# GWLSensor_v10.net
KiCad netlist of a schematic drawn in EAGLE
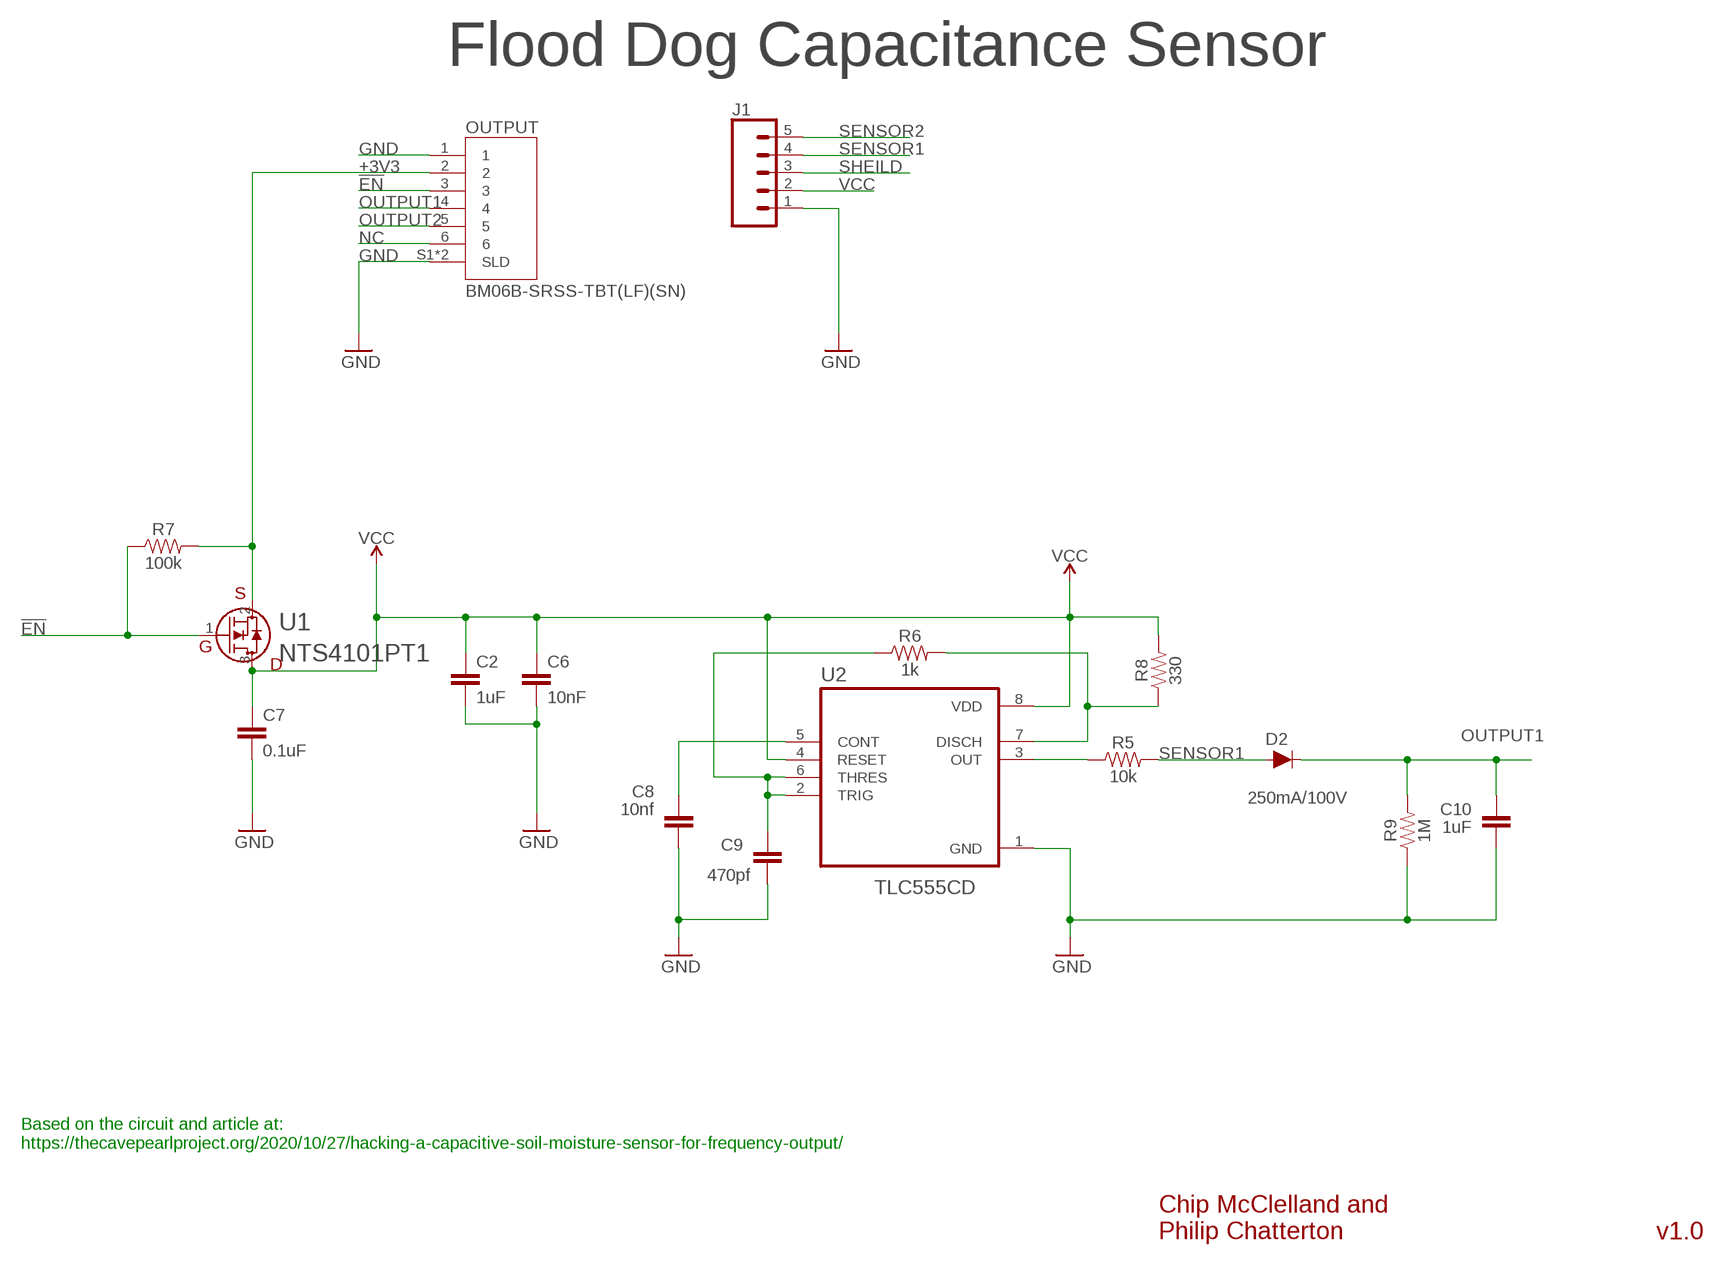
[diagram p0: schematic, sheet 1]

(export (version "E")
  (design (tool "Eeschema 10.0.6"))
  (components
    (comp (ref "C2")
      (value "1uF")
      (footprint "eagle-import:0805@1")
      (fields (field (name "HOUSEPART") "yes") (field (name "MPN") "MF-CAP-0805-1uF"))
      (libsource (lib "eagle-import") (part "CAP-MF-1UF-0805"))
    )
    (comp (ref "C6")
      (value "10nF")
      (footprint "eagle-import:0805@1")
      (fields (field (name "HOUSEPART") "NO") (field (name "MPN") "C0805X103K1RAC3316"))
      (libsource (lib "eagle-import") (part "CAP-10NF-0805"))
    )
    (comp (ref "C7")
      (value "0.1uF")
      (footprint "eagle-import:0805@1")
      (fields (field (name "HOUSEPART") "YES") (field (name "MPN") "MF-CAP-0805-0.1uF"))
      (libsource (lib "eagle-import") (part "CAP-MF-0.1UF-0805"))
    )
    (comp (ref "C8")
      (value "10nf")
      (footprint "eagle-import:C0805")
      (libsource (lib "eagle-import") (part "C-EUC0805"))
    )
    (comp (ref "C9")
      (value "470pf")
      (footprint "eagle-import:C0805")
      (libsource (lib "eagle-import") (part "C-EUC0805"))
    )
    (comp (ref "C10")
      (value "1uF")
      (footprint "eagle-import:C0805")
      (libsource (lib "eagle-import") (part "C-EUC0805"))
    )
    (comp (ref "D2")
      (value "250mA/100V")
      (footprint "eagle-import:SOD-323")
      (fields (field (name "MPN") "BAS16HT1G"))
      (libsource (lib "eagle-import") (part "DIODE-BAS16J"))
    )
    (comp (ref "J1")
      (value "CONN_05SCREW")
      (footprint "eagle-import:SCREWTERMINAL-3.5MM-5")
      (libsource (lib "eagle-import") (part "CONN_05SCREW"))
    )
    (comp (ref "OUTPUT")
      (value "BM06B-SRSS-TBT(LF)(SN)")
      (footprint "eagle-import:JST_BM06B-SRSS-TB(LF)(SN)")
      (libsource (lib "eagle-import") (part "BM06B-SRSS-TBT(LF)(SN)"))
    )
    (comp (ref "R5")
      (value "10k")
      (footprint "eagle-import:0805")
      (fields (field (name "MPN") "MF-RES-0805-10K"))
      (libsource (lib "eagle-import") (part "RESISTOR-MF-10K-0805"))
    )
    (comp (ref "R6")
      (value "1k")
      (footprint "eagle-import:0805")
      (fields (field (name "HOUSEPART") "YES") (field (name "MPN") "MF-RES-0805-1K"))
      (libsource (lib "eagle-import") (part "RESISTOR-MF-1K-0805"))
    )
    (comp (ref "R7")
      (value "100k")
      (footprint "eagle-import:0805")
      (fields (field (name "MPN") "MF-RES-0805-100K") (field (name "MPN_1") "MF-RES-0805-100K"))
      (libsource (lib "eagle-import") (part "RESISTOR-MF-100K-0805"))
    )
    (comp (ref "R8")
      (value "330")
      (footprint "eagle-import:0805")
      (fields (field (name "HOUSEPART") "YES") (field (name "MPN") "MF-RES-0805-330"))
      (libsource (lib "eagle-import") (part "RESISTOR-MF-330-0805"))
    )
    (comp (ref "R9")
      (value "1M")
      (footprint "eagle-import:0805")
      (fields (field (name "HOUSEPART") "YES") (field (name "MPN") "MF-RES-0805-1K"))
      (libsource (lib "eagle-import") (part "RESISTOR-MF-1K-0805"))
    )
    (comp (ref "U1")
      (value "NTS4101PT1")
      (footprint "eagle-import:SOT_101PT1_ONS")
      (libsource (lib "eagle-import") (part "NTS4101PT1"))
    )
    (comp (ref "U2")
      (value "TLC555CD")
      (footprint "eagle-import:SOIC127P599X175-8N")
      (fields (field (name "DIGI-KEY_PART_NUMBER") "296-52992-ND") (field (name "MF") "Texas Instruments"))
      (libsource (lib "eagle-import") (part "TLC555CD"))
    )
  )
  (nets
    (net (code "1") (name "/+3V3") (class "Default")
      (node (ref "OUTPUT") (pin "2") (pinfunction "2_2") (pintype "passive"))
      (node (ref "R7") (pin "2") (pinfunction "2_2") (pintype "passive"))
      (node (ref "U1") (pin "2") (pinfunction "S_2") (pintype "passive"))
    )
    (net (code "2") (name "/NC") (class "Default")
      (node (ref "OUTPUT") (pin "6") (pinfunction "6_6") (pintype "passive"))
    )
    (net (code "3") (name "/OUTPUT1") (class "Default")
      (node (ref "C10") (pin "2") (pinfunction "2_2") (pintype "passive"))
      (node (ref "D2") (pin "C") (pinfunction "C_C") (pintype "passive"))
      (node (ref "OUTPUT") (pin "4") (pinfunction "4_4") (pintype "passive"))
      (node (ref "R9") (pin "2") (pinfunction "2_2") (pintype "passive"))
    )
    (net (code "4") (name "/OUTPUT2") (class "Default")
      (node (ref "OUTPUT") (pin "5") (pinfunction "5_5") (pintype "passive"))
    )
    (net (code "5") (name "/SENSOR1") (class "Default")
      (node (ref "D2") (pin "A") (pinfunction "A_A") (pintype "passive"))
      (node (ref "J1") (pin "4") (pinfunction "4_4") (pintype "passive"))
      (node (ref "R5") (pin "2") (pinfunction "2_2") (pintype "passive"))
    )
    (net (code "6") (name "/SENSOR2") (class "Default")
      (node (ref "J1") (pin "5") (pinfunction "5_5") (pintype "passive"))
    )
    (net (code "7") (name "/SHEILD") (class "Default")
      (node (ref "J1") (pin "3") (pinfunction "3_3") (pintype "passive"))
    )
    (net (code "8") (name "/~{EN}") (class "Default")
      (node (ref "OUTPUT") (pin "3") (pinfunction "3_3") (pintype "passive"))
      (node (ref "R7") (pin "1") (pinfunction "1_1") (pintype "passive"))
      (node (ref "U1") (pin "1") (pinfunction "G_1") (pintype "passive"))
    )
    (net (code "9") (name "GND") (class "Default")
      (node (ref "C10") (pin "1") (pinfunction "1_1") (pintype "passive"))
      (node (ref "C2") (pin "2") (pinfunction "2_2") (pintype "passive"))
      (node (ref "C6") (pin "2") (pinfunction "2_2") (pintype "passive"))
      (node (ref "C7") (pin "2") (pinfunction "2_2") (pintype "passive"))
      (node (ref "C8") (pin "1") (pinfunction "1_1") (pintype "passive"))
      (node (ref "C9") (pin "1") (pinfunction "1_1") (pintype "passive"))
      (node (ref "J1") (pin "1") (pinfunction "1_1") (pintype "passive"))
      (node (ref "OUTPUT") (pin "1") (pinfunction "1_1") (pintype "passive"))
      (node (ref "OUTPUT") (pin "S1") (pinfunction "SLD_S1") (pintype "passive"))
      (node (ref "OUTPUT") (pin "S2") (pinfunction "SLD_S2") (pintype "passive"))
      (node (ref "R9") (pin "1") (pinfunction "1_1") (pintype "passive"))
      (node (ref "U2") (pin "1") (pinfunction "GND_1") (pintype "power_in"))
    )
    (net (code "10") (name "Net-(U2-CONT)") (class "Default")
      (node (ref "C8") (pin "2") (pinfunction "2_2") (pintype "passive"))
      (node (ref "U2") (pin "5") (pinfunction "CONT_5") (pintype "input"))
    )
    (net (code "11") (name "Net-(U2-DISCH)") (class "Default")
      (node (ref "R6") (pin "2") (pinfunction "2_2") (pintype "passive"))
      (node (ref "R8") (pin "1") (pinfunction "1_1") (pintype "passive"))
      (node (ref "U2") (pin "7") (pinfunction "DISCH_7") (pintype "output"))
    )
    (net (code "12") (name "Net-(U2-OUT)") (class "Default")
      (node (ref "R5") (pin "1") (pinfunction "1_1") (pintype "passive"))
      (node (ref "U2") (pin "3") (pinfunction "OUT_3") (pintype "output"))
    )
    (net (code "13") (name "Net-(U2-THRES)") (class "Default")
      (node (ref "C9") (pin "2") (pinfunction "2_2") (pintype "passive"))
      (node (ref "R6") (pin "1") (pinfunction "1_1") (pintype "passive"))
      (node (ref "U2") (pin "2") (pinfunction "TRIG_2") (pintype "input"))
      (node (ref "U2") (pin "6") (pinfunction "THRES_6") (pintype "input"))
    )
    (net (code "14") (name "VCC") (class "Default")
      (node (ref "C2") (pin "1") (pinfunction "1_1") (pintype "passive"))
      (node (ref "C6") (pin "1") (pinfunction "1_1") (pintype "passive"))
      (node (ref "C7") (pin "1") (pinfunction "1_1") (pintype "passive"))
      (node (ref "J1") (pin "2") (pinfunction "2_2") (pintype "passive"))
      (node (ref "R8") (pin "2") (pinfunction "2_2") (pintype "passive"))
      (node (ref "U1") (pin "3") (pinfunction "D_3") (pintype "passive"))
      (node (ref "U2") (pin "4") (pinfunction "RESET_4") (pintype "input"))
      (node (ref "U2") (pin "8") (pinfunction "VDD_8") (pintype "power_in"))
    )
  )
)
